# IM69D130_MEMS_Microphone.net
KiCad netlist of a schematic drawn in Altium Designer
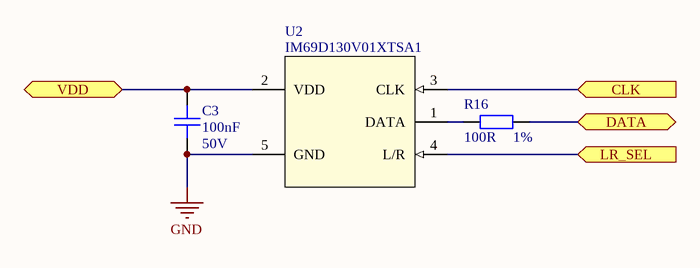
[diagram p0: IM69D130_MEMS_Microphone.SchDoc]

(export (version "E")
  (design (tool "Eeschema 10.0.6"))
  (components
    (comp (ref "C3")
      (value "CAP CER 0.1UF 50V X7R 0402")
      (footprint "C0402")
      (description "0.1µF ±10% 50V Ceramic Capacitor X7R 0402 (1005 Metric)")
      (fields
        (field (name "MANUFACTURER") "TDK")
        (field (name "MANUFACTURER PART NUMBER") "CGA2B3X7R1H104K050BB")
        (field (name "CAPACITANCE") "100nF")
        (field (name "VOLTAGE") "50V")
      )
      (libsource (lib "capacitors_smd") (part "CAP CER 0.1UF 50V X7R 0402"))
    )
    (comp (ref "R16")
      (value "RES SMD 100 OHM 1% 1/16W 0402")
      (footprint "0402R")
      (description "100 Ohms ±1% 0.063W, 1/16W Chip Resistor 0402 (1005 Metric) Moisture Resistant Thick Film")
      (fields
        (field (name "MANUFACTURER") "Yageo")
        (field (name "MANUFACTURER PART NUMBER") "RC0402FR-07100RL")
        (field (name "TOLERANCE") "1%")
        (field (name "RESISTANCE") "100R")
      )
      (libsource (lib "resistors_smd") (part "RES SMD 100 OHM 1% 1/16W 0402"))
    )
    (comp (ref "U2")
      (value "IM69D130V01XTSA1")
      (footprint "MIC_IM69D130V01XTSA1")
      (fields (field (name "MANUFACTURER") "Infineon"))
      (libsource (lib "BLDC_Motor_Driver") (part "IC IM69D130 MICROPHONE MEMS DIGITAL PDM OMNI"))
    )
  )
  (nets
    (net (code "1") (name "/CLK") (class "Default")
      (node (ref "U2") (pin "3") (pinfunction "CLK_3") (pintype "input"))
    )
    (net (code "2") (name "/DATA") (class "Default")
      (node (ref "R16") (pin "1") (pinfunction "1_1") (pintype "passive"))
    )
    (net (code "3") (name "/LR_SEL") (class "Default")
      (node (ref "U2") (pin "4") (pinfunction "L/R_4") (pintype "input"))
    )
    (net (code "4") (name "/VDD") (class "Default")
      (node (ref "C3") (pin "2") (pinfunction "2_2") (pintype "passive"))
      (node (ref "U2") (pin "2") (pinfunction "VDD_2") (pintype "power_in"))
    )
    (net (code "5") (name "GND") (class "Default")
      (node (ref "C3") (pin "1") (pinfunction "1_1") (pintype "passive"))
      (node (ref "U2") (pin "5") (pinfunction "GND_5") (pintype "power_in"))
    )
    (net (code "6") (name "Net-(U2-DATA)") (class "Default")
      (node (ref "R16") (pin "2") (pinfunction "2_2") (pintype "passive"))
      (node (ref "U2") (pin "1") (pinfunction "DATA_1") (pintype "tri_state"))
    )
  )
)
